# midi_block_R2_1.net
KiCad netlist of a schematic drawn in EAGLE
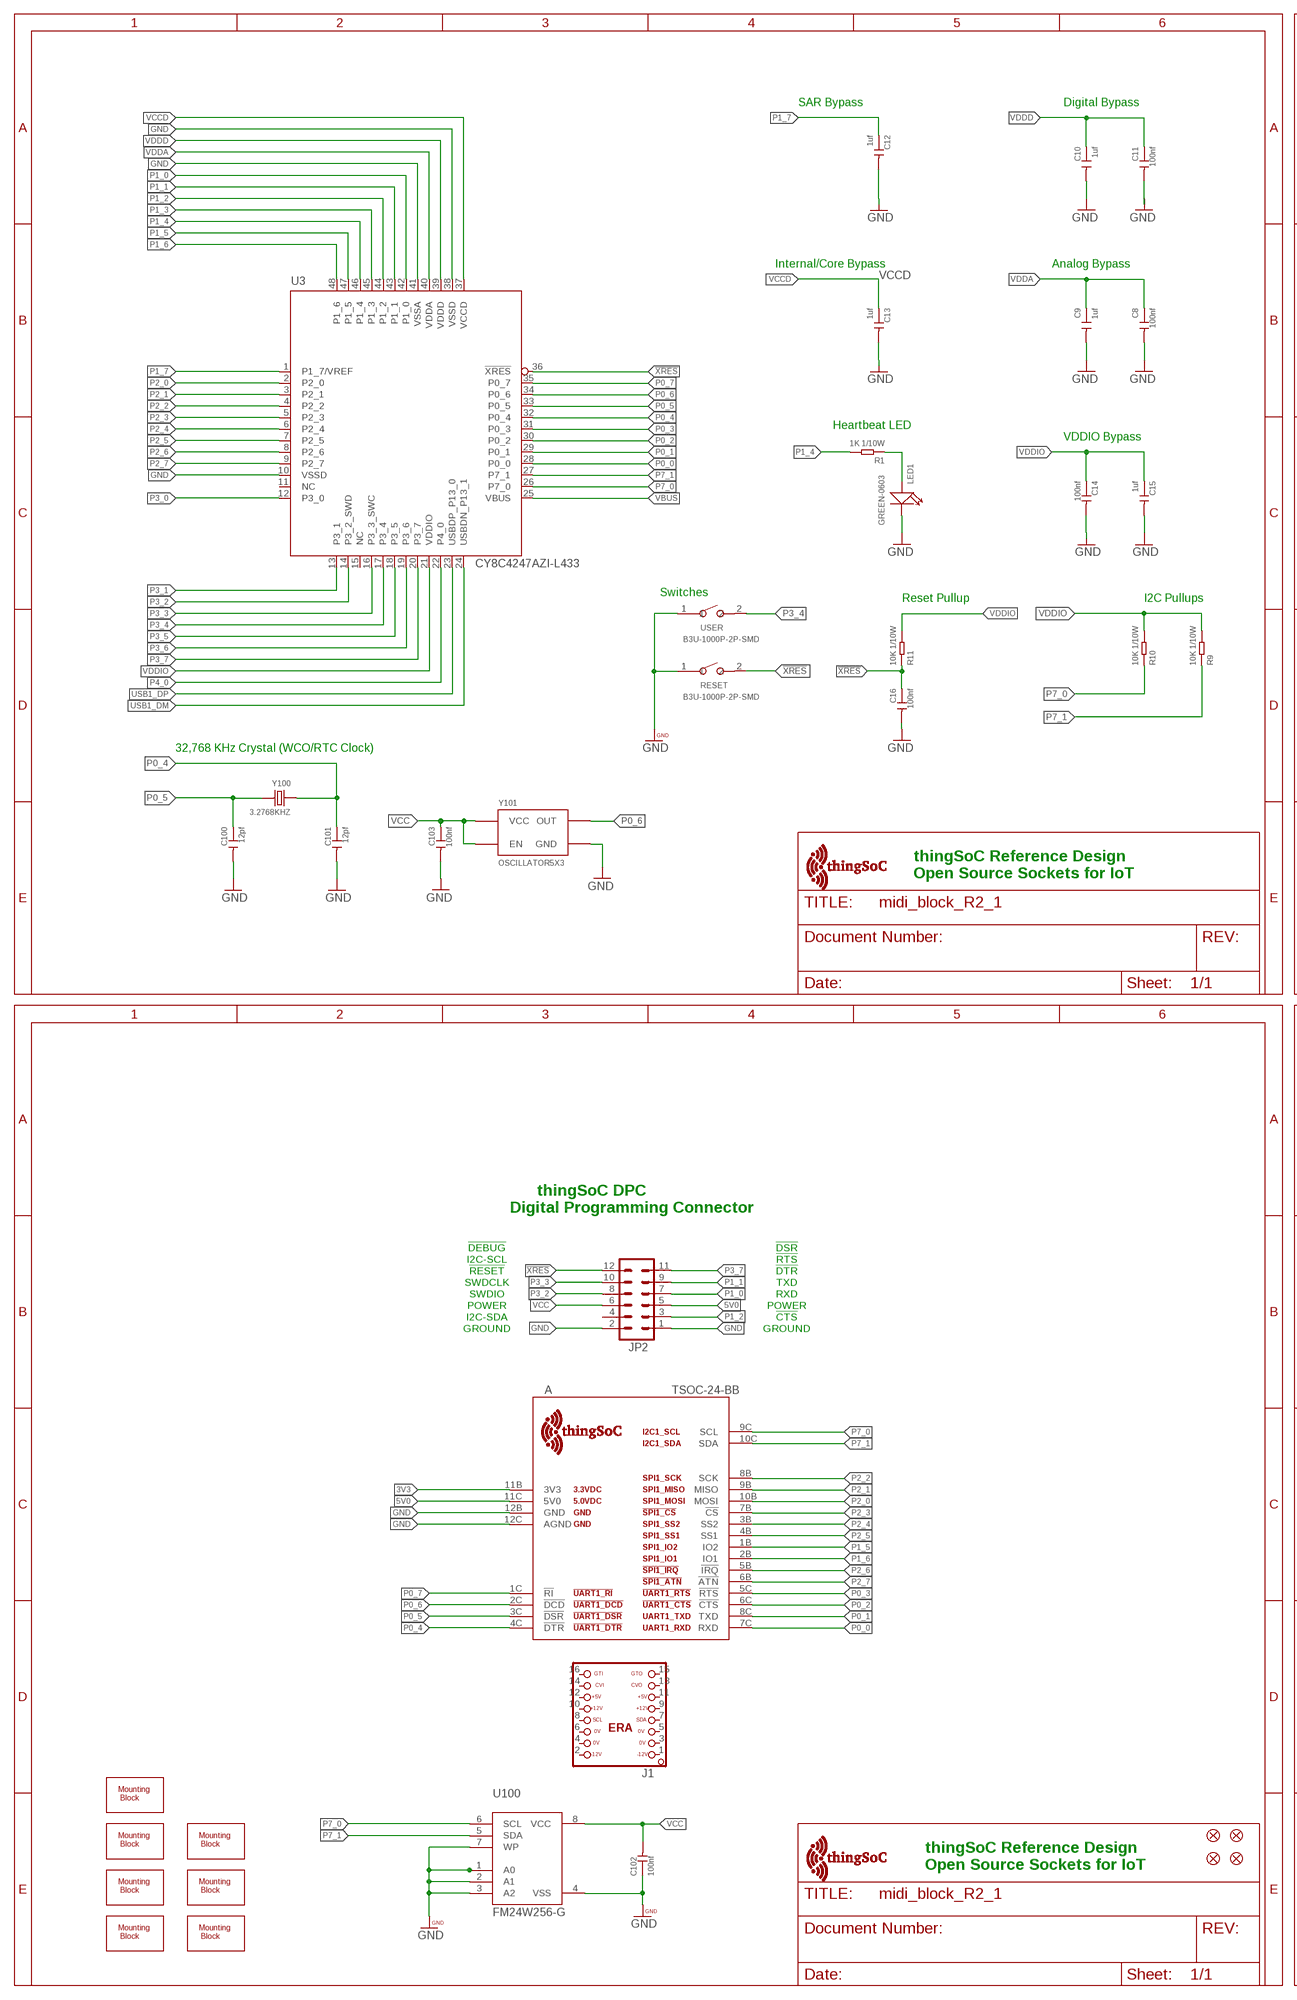
[diagram p0: schematic, sheet 1, part 1 of 2]
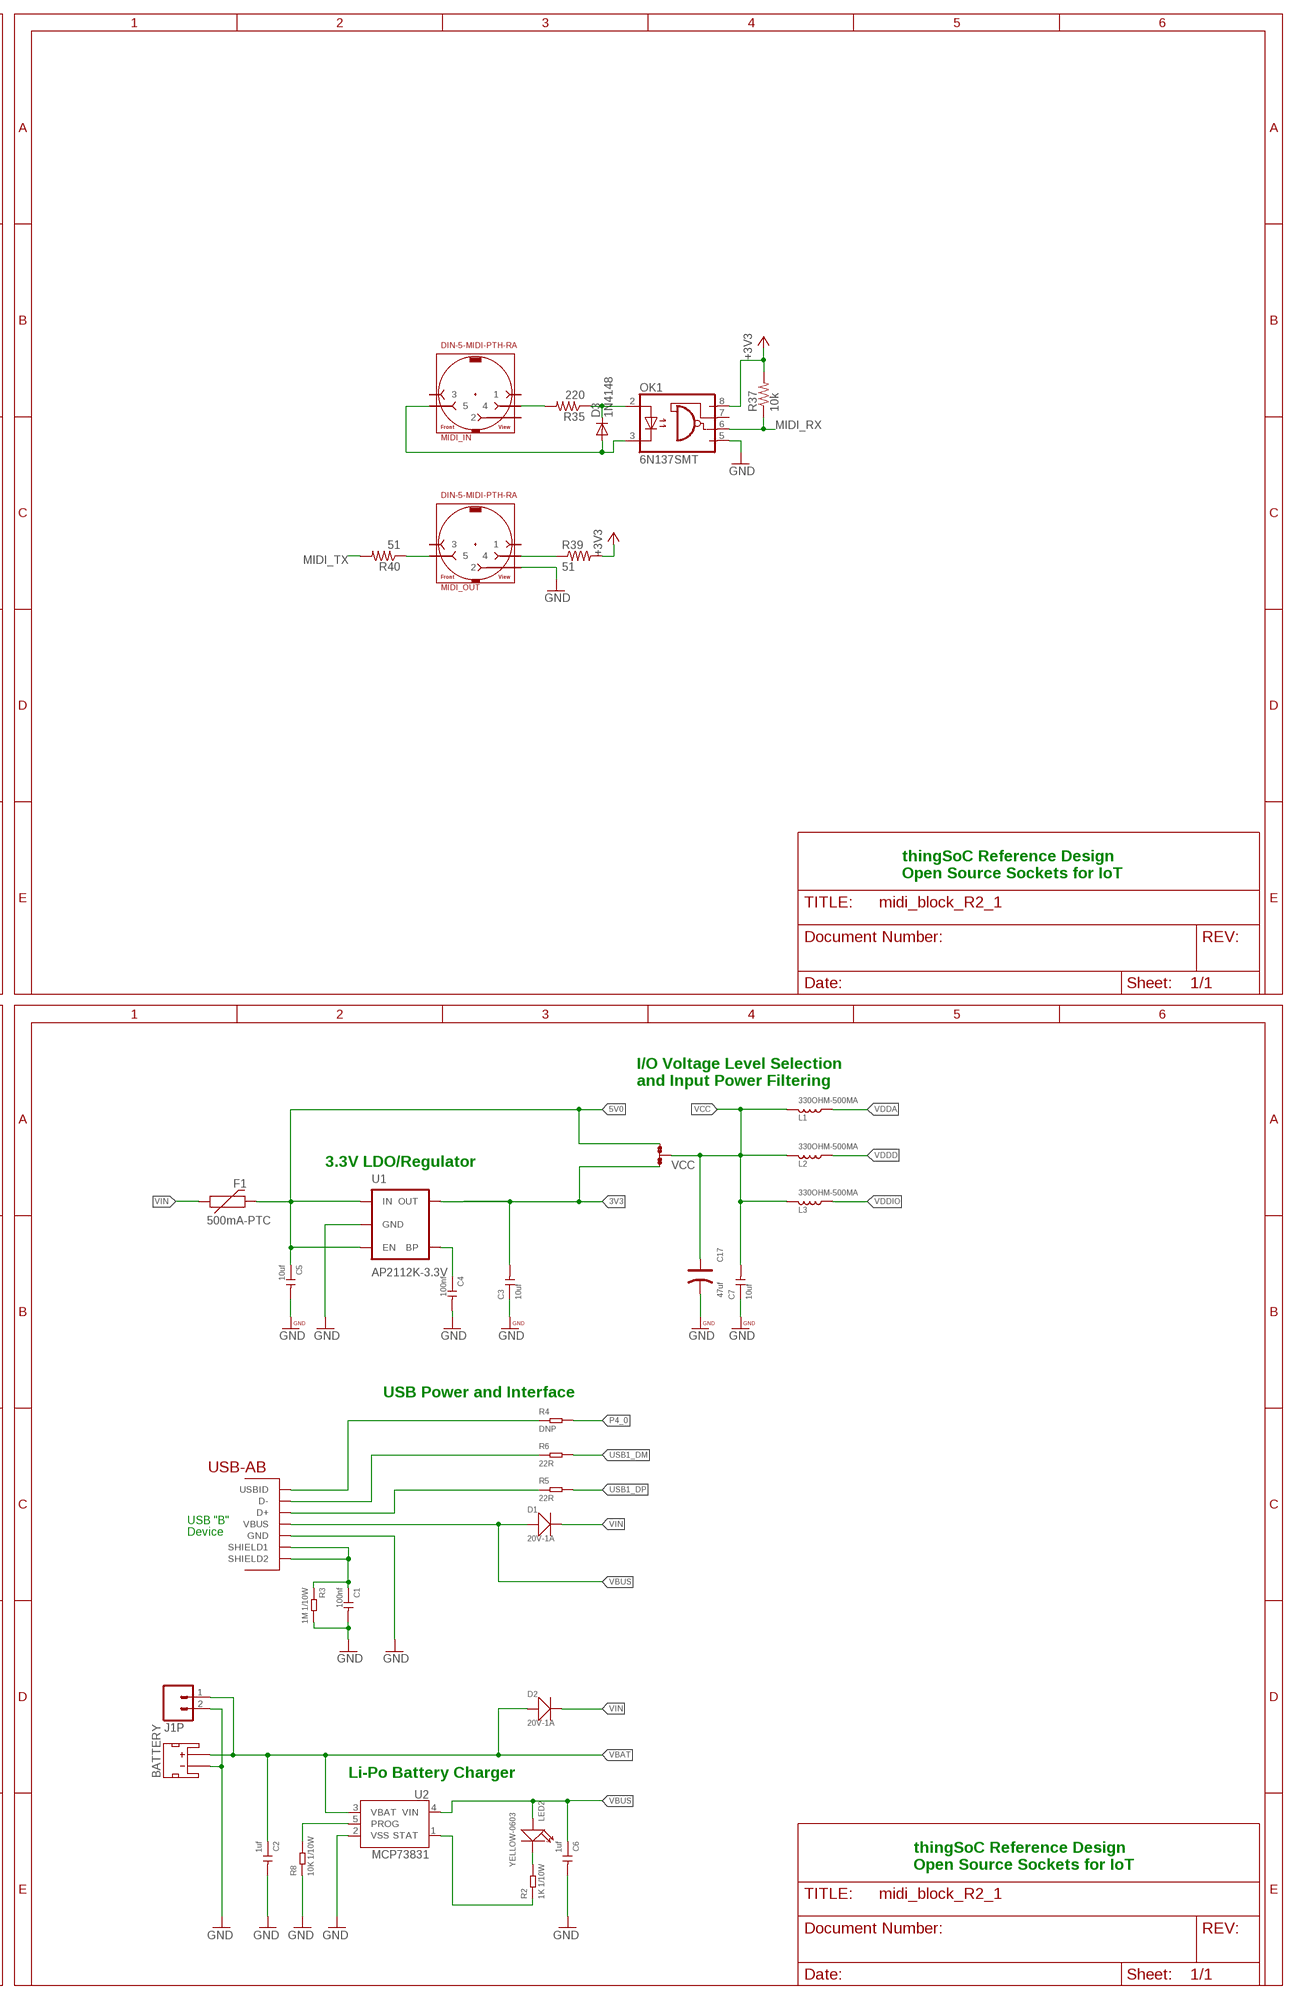
[diagram p1: schematic, sheet 1, part 2 of 2]

(export (version "E")
  (design (tool "Eeschema 10.0.6"))
  (components
    (comp (ref "A")
      (value "TSOC-24-BB")
      (footprint "eagle-import:TSOC-BB-S24")
      (libsource (lib "eagle-import") (part "TSOC-24-BB"))
    )
    (comp (ref "BATTERY")
      (value "JST_2MM_MALE")
      (footprint "eagle-import:JST-2-SMD")
      (libsource (lib "eagle-import") (part "JST_2MM_MALE"))
    )
    (comp (ref "C1")
      (value "100nf")
      (footprint "eagle-import:C0603")
      (fields (field (name "MPN") "CC0603KRX7R9BB104"))
      (libsource (lib "eagle-import") (part "CERAMIC-100NF-50V-10%-X7R(0603)"))
    )
    (comp (ref "C2")
      (value "1uf")
      (footprint "eagle-import:C0603")
      (fields (field (name "MPN") "CC0603KRX7R8BB105"))
      (libsource (lib "eagle-import") (part "CERAMIC-1UF-25V-10%-X7R(0603)"))
    )
    (comp (ref "C3")
      (value "10uf")
      (footprint "eagle-import:C0603")
      (fields (field (name "MPN") "CC0603KRX5R6BB106"))
      (libsource (lib "eagle-import") (part "CERAMIC-10UF-10V-10%-X5R(0603)"))
    )
    (comp (ref "C4")
      (value "100nf")
      (footprint "eagle-import:C0603")
      (fields (field (name "MPN") "CC0603KRX7R9BB104"))
      (libsource (lib "eagle-import") (part "CERAMIC-100NF-50V-10%-X7R(0603)"))
    )
    (comp (ref "C5")
      (value "10uf")
      (footprint "eagle-import:C0603")
      (fields (field (name "MPN") "CC0603KRX5R6BB106"))
      (libsource (lib "eagle-import") (part "CERAMIC-10UF-10V-10%-X5R(0603)"))
    )
    (comp (ref "C6")
      (value "1uf")
      (footprint "eagle-import:C0603")
      (fields (field (name "MPN") "CC0603KRX7R8BB105"))
      (libsource (lib "eagle-import") (part "CERAMIC-1UF-25V-10%-X7R(0603)"))
    )
    (comp (ref "C7")
      (value "10uf")
      (footprint "eagle-import:C0603")
      (fields (field (name "MPN") "CC0603KRX5R6BB106"))
      (libsource (lib "eagle-import") (part "CERAMIC-10UF-10V-10%-X5R(0603)"))
    )
    (comp (ref "C8")
      (value "100nf")
      (footprint "eagle-import:C0603")
      (fields (field (name "MPN") "CC0603KRX7R9BB104"))
      (libsource (lib "eagle-import") (part "CERAMIC-100NF-50V-10%-X7R(0603)"))
    )
    (comp (ref "C9")
      (value "1uf")
      (footprint "eagle-import:C0603")
      (fields (field (name "MPN") "CC0603KRX7R8BB105"))
      (libsource (lib "eagle-import") (part "CERAMIC-1UF-25V-10%-X7R(0603)"))
    )
    (comp (ref "C10")
      (value "1uf")
      (footprint "eagle-import:C0603")
      (fields (field (name "MPN") "CC0603KRX7R8BB105"))
      (libsource (lib "eagle-import") (part "CERAMIC-1UF-25V-10%-X7R(0603)"))
    )
    (comp (ref "C11")
      (value "100nf")
      (footprint "eagle-import:C0603")
      (fields (field (name "MPN") "CC0603KRX7R9BB104"))
      (libsource (lib "eagle-import") (part "CERAMIC-100NF-50V-10%-X7R(0603)"))
    )
    (comp (ref "C12")
      (value "1uf")
      (footprint "eagle-import:C0603")
      (fields (field (name "MPN") "CC0603KRX7R8BB105"))
      (libsource (lib "eagle-import") (part "CERAMIC-1UF-25V-10%-X7R(0603)"))
    )
    (comp (ref "C13")
      (value "1uf")
      (footprint "eagle-import:C0603")
      (fields (field (name "MPN") "CC0603KRX7R8BB105"))
      (libsource (lib "eagle-import") (part "CERAMIC-1UF-25V-10%-X7R(0603)"))
    )
    (comp (ref "C14")
      (value "100nf")
      (footprint "eagle-import:C0603")
      (fields (field (name "MPN") "CC0603KRX7R9BB104"))
      (libsource (lib "eagle-import") (part "CERAMIC-100NF-50V-10%-X7R(0603)"))
    )
    (comp (ref "C15")
      (value "1uf")
      (footprint "eagle-import:C0603")
      (fields (field (name "MPN") "CC0603KRX7R8BB105"))
      (libsource (lib "eagle-import") (part "CERAMIC-1UF-25V-10%-X7R(0603)"))
    )
    (comp (ref "C16")
      (value "100nf")
      (footprint "eagle-import:C0603")
      (fields (field (name "MPN") "CC0603KRX7R9BB104"))
      (libsource (lib "eagle-import") (part "CERAMIC-100NF-50V-10%-X7R(0603)"))
    )
    (comp (ref "C17")
      (value "47uf")
      (footprint "eagle-import:AVX-A")
      (fields (field (name "MPN") "TAJA476*006#NJ"))
      (libsource (lib "eagle-import") (part "TANTALUM-SMD-47UF-6.3V(AVX-A)"))
    )
    (comp (ref "C100")
      (value "12pf")
      (footprint "eagle-import:C0603")
      (fields (field (name "MPN") "CC0603JRNPO9BN120"))
      (libsource (lib "eagle-import") (part "CERAMIC-12PF-50V-5%-NPO(0603)"))
    )
    (comp (ref "C101")
      (value "12pf")
      (footprint "eagle-import:C0603")
      (fields (field (name "MPN") "CC0603JRNPO9BN120"))
      (libsource (lib "eagle-import") (part "CERAMIC-12PF-50V-5%-NPO(0603)"))
    )
    (comp (ref "C102")
      (value "100nf")
      (footprint "eagle-import:C0603")
      (fields (field (name "MPN") "CC0603KRX7R9BB104"))
      (libsource (lib "eagle-import") (part "CERAMIC-100NF-50V-10%-X7R(0603)"))
    )
    (comp (ref "C103")
      (value "100nf")
      (footprint "eagle-import:C0603")
      (fields (field (name "MPN") "CC0603KRX7R9BB104"))
      (libsource (lib "eagle-import") (part "CERAMIC-100NF-50V-10%-X7R(0603)"))
    )
    (comp (ref "D1")
      (value "20V-1A")
      (footprint "eagle-import:SOD-123")
      (fields (field (name "MPN") "B5819W"))
      (libsource (lib "eagle-import") (part "SMD-DIODE-SCHOTTKY-20V-1A(SOD-123)"))
    )
    (comp (ref "D2")
      (value "20V-1A")
      (footprint "eagle-import:SOD-123")
      (fields (field (name "MPN") "B5819W"))
      (libsource (lib "eagle-import") (part "SMD-DIODE-SCHOTTKY-20V-1A(SOD-123)"))
    )
    (comp (ref "D3")
      (value "1N4148")
      (footprint "eagle-import:SOD323-W")
      (libsource (lib "eagle-import") (part "DIODE-SOD323-W"))
    )
    (comp (ref "F1")
      (value "500mA-PTC")
      (footprint "eagle-import:PTC-1206")
      (libsource (lib "eagle-import") (part "PTCSMD"))
    )
    (comp (ref "FID1")
      (value "FIDUCIALUFIDUCIAL")
      (footprint "eagle-import:MICRO-FIDUCIAL")
      (libsource (lib "eagle-import") (part "FIDUCIALUFIDUCIAL"))
    )
    (comp (ref "FID2")
      (value "FIDUCIALUFIDUCIAL")
      (footprint "eagle-import:MICRO-FIDUCIAL")
      (libsource (lib "eagle-import") (part "FIDUCIALUFIDUCIAL"))
    )
    (comp (ref "FID3")
      (value "FIDUCIALUFIDUCIAL")
      (footprint "eagle-import:MICRO-FIDUCIAL")
      (libsource (lib "eagle-import") (part "FIDUCIALUFIDUCIAL"))
    )
    (comp (ref "FID4")
      (value "FIDUCIALUFIDUCIAL")
      (footprint "eagle-import:MICRO-FIDUCIAL")
      (libsource (lib "eagle-import") (part "FIDUCIALUFIDUCIAL"))
    )
    (comp (ref "J1")
      (value "ERA-SMD")
      (footprint "eagle-import:ERA-SMD")
      (libsource (lib "eagle-import") (part "ERA-SMD"))
    )
    (comp (ref "J1P")
      (value "M02-JST-2-PTH-NO_SILK")
      (footprint "eagle-import:JST-2-PTH-NS")
      (libsource (lib "eagle-import") (part "M02-JST-2-PTH-NO_SILK"))
    )
    (comp (ref "JP2")
      (value "M06X2FEMALE-SMT")
      (footprint "eagle-import:2X6_SMD")
      (libsource (lib "eagle-import") (part "M06X2FEMALE-SMT"))
    )
    (comp (ref "L1")
      (value "330OHM-500MA")
      (footprint "eagle-import:L0603")
      (fields (field (name "MPN") "BLM18AG121SN1D"))
      (libsource (lib "eagle-import") (part "SMD-FERRITE-CHIP-120-OHM-500MA(0603)"))
    )
    (comp (ref "L2")
      (value "330OHM-500MA")
      (footprint "eagle-import:L0603")
      (fields (field (name "MPN") "BLM18AG121SN1D"))
      (libsource (lib "eagle-import") (part "SMD-FERRITE-CHIP-120-OHM-500MA(0603)"))
    )
    (comp (ref "L3")
      (value "330OHM-500MA")
      (footprint "eagle-import:L0603")
      (fields (field (name "MPN") "BLM18AG121SN1D"))
      (libsource (lib "eagle-import") (part "SMD-FERRITE-CHIP-120-OHM-500MA(0603)"))
    )
    (comp (ref "LED1")
      (value "GREEN-0603")
      (footprint "eagle-import:LED-0603")
      (fields (field (name "MPN") "19-217-G7C-AN1P2-3T"))
      (libsource (lib "eagle-import") (part "SMD-LED-CLEAR-GREEN(0603)"))
    )
    (comp (ref "LED2")
      (value "YELLOW-0603")
      (footprint "eagle-import:LED-0603")
      (fields (field (name "MPN") "19-217-Y5C-AM1N1VY-3T"))
      (libsource (lib "eagle-import") (part "SMD-LED-CLEAR-YELLOW(0603)"))
    )
    (comp (ref "MIDI_IN")
      (value "DIN-5-MIDI-PTH-RA")
      (footprint "eagle-import:DIN-5-PTH-RA-SUPPORT")
      (libsource (lib "eagle-import") (part "DIN-5-MIDI-PTH-RA"))
    )
    (comp (ref "MIDI_OUT")
      (value "DIN-5-MIDI-PTH-RA")
      (footprint "eagle-import:DIN-5-PTH-RA-SUPPORT")
      (libsource (lib "eagle-import") (part "DIN-5-MIDI-PTH-RA"))
    )
    (comp (ref "OK1")
      (value "6N137SMT")
      (footprint "eagle-import:DIL8-SMD")
      (libsource (lib "eagle-import") (part "6N137SMT"))
    )
    (comp (ref "R1")
      (value "1K 1/10W")
      (footprint "eagle-import:R0603")
      (fields (field (name "MPN") "RC0603JR-071KL"))
      (libsource (lib "eagle-import") (part "SMD-RES-1K-5%-1/10W(0603)"))
    )
    (comp (ref "R2")
      (value "1K 1/10W")
      (footprint "eagle-import:R0603")
      (fields (field (name "MPN") "RC0603JR-071KL"))
      (libsource (lib "eagle-import") (part "SMD-RES-1K-5%-1/10W(0603)"))
    )
    (comp (ref "R3")
      (value "1M 1/10W")
      (footprint "eagle-import:R0603")
      (fields (field (name "MPN") "RC0603JR-071ML"))
      (libsource (lib "eagle-import") (part "SMD-RES-1M-5%-1/10W(0603)"))
    )
    (comp (ref "R4")
      (value "DNP")
      (footprint "eagle-import:R0603")
      (fields (field (name "MPN") "RC0603JR-0722RL"))
      (libsource (lib "eagle-import") (part "SMD-RES-22R-5%-1/10W(0603)"))
    )
    (comp (ref "R5")
      (value "22R")
      (footprint "eagle-import:R0603")
      (fields (field (name "MPN") "RC0603JR-0722RL"))
      (libsource (lib "eagle-import") (part "SMD-RES-22R-5%-1/10W(0603)"))
    )
    (comp (ref "R6")
      (value "22R")
      (footprint "eagle-import:R0603")
      (fields (field (name "MPN") "RC0603JR-0722RL"))
      (libsource (lib "eagle-import") (part "SMD-RES-22R-5%-1/10W(0603)"))
    )
    (comp (ref "R8")
      (value "10K 1/10W")
      (footprint "eagle-import:R0603")
      (fields (field (name "MPN") "RC0603JR-0710KL"))
      (libsource (lib "eagle-import") (part "SMD-RES-10K-5%-1/10W(0603)"))
    )
    (comp (ref "R9")
      (value "10K 1/10W")
      (footprint "eagle-import:R0603")
      (fields (field (name "MPN") "RC0603JR-0710KL"))
      (libsource (lib "eagle-import") (part "SMD-RES-10K-5%-1/10W(0603)"))
    )
    (comp (ref "R10")
      (value "10K 1/10W")
      (footprint "eagle-import:R0603")
      (fields (field (name "MPN") "RC0603JR-0710KL"))
      (libsource (lib "eagle-import") (part "SMD-RES-10K-5%-1/10W(0603)"))
    )
    (comp (ref "R11")
      (value "10K 1/10W")
      (footprint "eagle-import:R0603")
      (fields (field (name "MPN") "RC0603JR-0710KL"))
      (libsource (lib "eagle-import") (part "SMD-RES-10K-5%-1/10W(0603)"))
    )
    (comp (ref "R35")
      (value "220")
      (footprint "eagle-import:R0603")
      (libsource (lib "eagle-import") (part "R-US_R0603"))
    )
    (comp (ref "R37")
      (value "10k")
      (footprint "eagle-import:R0603")
      (libsource (lib "eagle-import") (part "R-US_R0603"))
    )
    (comp (ref "R39")
      (value "51")
      (footprint "eagle-import:R0603")
      (libsource (lib "eagle-import") (part "R-US_R0603"))
    )
    (comp (ref "R40")
      (value "51")
      (footprint "eagle-import:R0603")
      (libsource (lib "eagle-import") (part "R-US_R0603"))
    )
    (comp (ref "RESET")
      (value "B3U-1000P-2P-SMD")
      (footprint "eagle-import:SW2-2.6-3.0X2.5X1.2+0.4MM")
      (libsource (lib "eagle-import") (part "SMD-BUTTON(2P-3.0X2.5X1.2+0.4MM)-B3U-1000P-2P-SMD"))
    )
    (comp (ref "U$1")
      (value "PCB-MB-SIDE")
      (footprint "eagle-import:PCB-MB-01-SIDE")
      (libsource (lib "eagle-import") (part "PCB-MB-SIDE"))
    )
    (comp (ref "U$7")
      (value "PCB-MB-SIDE")
      (footprint "eagle-import:PCB-MB-01-SIDE")
      (libsource (lib "eagle-import") (part "PCB-MB-SIDE"))
    )
    (comp (ref "U$8")
      (value "PCB-MB-SIDE")
      (footprint "eagle-import:PCB-MB-01-SIDE")
      (libsource (lib "eagle-import") (part "PCB-MB-SIDE"))
    )
    (comp (ref "U$9")
      (value "PCB-MB-SIDE")
      (footprint "eagle-import:PCB-MB-01-SIDE")
      (libsource (lib "eagle-import") (part "PCB-MB-SIDE"))
    )
    (comp (ref "U$10")
      (value "PCB-MB-SIDE")
      (footprint "eagle-import:PCB-MB-01-SIDE")
      (libsource (lib "eagle-import") (part "PCB-MB-SIDE"))
    )
    (comp (ref "U$11")
      (value "PCB-MB-SIDE")
      (footprint "eagle-import:PCB-MB-01-SIDE")
      (libsource (lib "eagle-import") (part "PCB-MB-SIDE"))
    )
    (comp (ref "U$12")
      (value "PCB-MB-SIDE")
      (footprint "eagle-import:PCB-MB-01-SIDE")
      (libsource (lib "eagle-import") (part "PCB-MB-SIDE"))
    )
    (comp (ref "U$100")
      (value "TSOC-LOGO-LRG")
      (footprint "eagle-import:TSOC-LOGO-LRG")
      (libsource (lib "eagle-import") (part "TSOC-LOGO-LRG"))
    )
    (comp (ref "U$101")
      (value "TSOC-LOGO-SMALL")
      (footprint "eagle-import:TSOC-LOGO-SML")
      (libsource (lib "eagle-import") (part "TSOC-LOGO-SMALL"))
    )
    (comp (ref "U1")
      (value "AP2112K-3.3V")
      (footprint "eagle-import:SOT23-5")
      (libsource (lib "eagle-import") (part "V_REG_LDOSMD"))
    )
    (comp (ref "U2")
      (value "MCP73831")
      (footprint "eagle-import:SOT23-5")
      (libsource (lib "eagle-import") (part "MCP73831"))
    )
    (comp (ref "U3")
      (value "CY8C4247AZI-L433")
      (footprint "eagle-import:TQFP-7X7-48")
      (libsource (lib "eagle-import") (part "CY8C4247AZI-L433"))
    )
    (comp (ref "U100")
      (value "FM24W256-G")
      (footprint "eagle-import:SO08")
      (libsource (lib "eagle-import") (part "FM24W256-G"))
    )
    (comp (ref "USB")
      (value "USB_AB")
      (footprint "eagle-import:USB-AB-MICRO-SMD")
      (libsource (lib "eagle-import") (part "USB_AB"))
    )
    (comp (ref "USER")
      (value "B3U-1000P-2P-SMD")
      (footprint "eagle-import:SW2-2.6-3.0X2.5X1.2+0.4MM")
      (libsource (lib "eagle-import") (part "SMD-BUTTON(2P-3.0X2.5X1.2+0.4MM)-B3U-1000P-2P-SMD"))
    )
    (comp (ref "VCC")
      (value "JMP-3-1_2")
      (footprint "eagle-import:JMP-3-1_2")
      (libsource (lib "eagle-import") (part "JMP-3-1_2"))
    )
    (comp (ref "Y100")
      (value "3.2768KHZ")
      (footprint "eagle-import:X2-SMD-L2.0X1.2X0.55MM")
      (fields (field (name "MPN") "FC-12M"))
      (libsource (lib "eagle-import") (part "SMD-CRYSTAL-32.768KHZ-12.5PF-20PPM-90K(2P-L2.0X1.2MM)"))
    )
    (comp (ref "Y101")
      (value "OSCILLATOR5X3")
      (footprint "eagle-import:CRYSTAL-SMD-5X3")
      (libsource (lib "eagle-import") (part "OSCILLATOR5X3"))
    )
  )
  (nets
    (net (code "1") (name "+3V3") (class "Default")
      (node (ref "OK1") (pin "8") (pinfunction "VCC_8") (pintype "passive"))
      (node (ref "R37") (pin "2") (pinfunction "2_2") (pintype "passive"))
      (node (ref "R39") (pin "2") (pinfunction "2_2") (pintype "passive"))
    )
    (net (code "2") (name "/MIDI_RX") (class "Default")
      (node (ref "OK1") (pin "6") (pinfunction "VO_6") (pintype "passive"))
      (node (ref "R37") (pin "1") (pinfunction "1_1") (pintype "passive"))
    )
    (net (code "3") (name "/MIDI_TX") (class "Default")
      (node (ref "R40") (pin "2") (pinfunction "2_2") (pintype "passive"))
    )
    (net (code "4") (name "/~{XRES}") (class "Default")
      (node (ref "C16") (pin "1") (pinfunction "1_1") (pintype "passive"))
      (node (ref "JP2") (pin "12") (pinfunction "12_12") (pintype "passive"))
      (node (ref "R11") (pin "1") (pinfunction "1_1") (pintype "passive"))
      (node (ref "RESET") (pin "2") (pinfunction "2_2") (pintype "bidirectional"))
      (node (ref "U3") (pin "36") (pinfunction "~{XRES}_36") (pintype "bidirectional"))
    )
    (net (code "5") (name "3V3") (class "Default")
      (node (ref "A") (pin "11B") (pinfunction "3V3_11B") (pintype "bidirectional"))
      (node (ref "C3") (pin "2") (pinfunction "2_2") (pintype "passive"))
      (node (ref "U1") (pin "5") (pinfunction "OUT_5") (pintype "passive"))
      (node (ref "VCC") (pin "1") (pinfunction "1_1") (pintype "passive"))
    )
    (net (code "6") (name "5V0") (class "Default")
      (node (ref "A") (pin "11C") (pinfunction "5V0_11C") (pintype "bidirectional"))
      (node (ref "C5") (pin "1") (pinfunction "1_1") (pintype "passive"))
      (node (ref "F1") (pin "2") (pinfunction "2_2") (pintype "bidirectional"))
      (node (ref "JP2") (pin "5") (pinfunction "5_5") (pintype "passive"))
      (node (ref "U1") (pin "1") (pinfunction "IN_1") (pintype "input"))
      (node (ref "U1") (pin "3") (pinfunction "EN_3") (pintype "input"))
      (node (ref "VCC") (pin "3") (pinfunction "3_3") (pintype "passive"))
    )
    (net (code "7") (name "GND") (class "Default")
      (node (ref "A") (pin "12B") (pinfunction "GND_12B") (pintype "bidirectional"))
      (node (ref "A") (pin "12C") (pinfunction "AGND_12C") (pintype "bidirectional"))
      (node (ref "BATTERY") (pin "1") (pinfunction "-_1") (pintype "bidirectional"))
      (node (ref "C1") (pin "2") (pinfunction "2_2") (pintype "passive"))
      (node (ref "C10") (pin "2") (pinfunction "2_2") (pintype "passive"))
      (node (ref "C100") (pin "2") (pinfunction "2_2") (pintype "passive"))
      (node (ref "C101") (pin "2") (pinfunction "2_2") (pintype "passive"))
      (node (ref "C102") (pin "1") (pinfunction "1_1") (pintype "passive"))
      (node (ref "C103") (pin "2") (pinfunction "2_2") (pintype "passive"))
      (node (ref "C11") (pin "2") (pinfunction "2_2") (pintype "passive"))
      (node (ref "C12") (pin "2") (pinfunction "2_2") (pintype "passive"))
      (node (ref "C13") (pin "2") (pinfunction "2_2") (pintype "passive"))
      (node (ref "C14") (pin "2") (pinfunction "2_2") (pintype "passive"))
      (node (ref "C15") (pin "2") (pinfunction "2_2") (pintype "passive"))
      (node (ref "C16") (pin "2") (pinfunction "2_2") (pintype "passive"))
      (node (ref "C17") (pin "-") (pinfunction "-_-") (pintype "passive"))
      (node (ref "C2") (pin "2") (pinfunction "2_2") (pintype "passive"))
      (node (ref "C3") (pin "1") (pinfunction "1_1") (pintype "passive"))
      (node (ref "C4") (pin "2") (pinfunction "2_2") (pintype "passive"))
      (node (ref "C5") (pin "2") (pinfunction "2_2") (pintype "passive"))
      (node (ref "C6") (pin "2") (pinfunction "2_2") (pintype "passive"))
      (node (ref "C7") (pin "1") (pinfunction "1_1") (pintype "passive"))
      (node (ref "C8") (pin "2") (pinfunction "2_2") (pintype "passive"))
      (node (ref "C9") (pin "2") (pinfunction "2_2") (pintype "passive"))
      (node (ref "J1P") (pin "2") (pinfunction "2_2") (pintype "passive"))
      (node (ref "JP2") (pin "1") (pinfunction "1_1") (pintype "passive"))
      (node (ref "JP2") (pin "2") (pinfunction "2_2") (pintype "passive"))
      (node (ref "LED1") (pin "-") (pinfunction "-_-") (pintype "passive"))
      (node (ref "MIDI_OUT") (pin "2") (pinfunction "2_2") (pintype "bidirectional"))
      (node (ref "OK1") (pin "5") (pinfunction "GND_5") (pintype "passive"))
      (node (ref "R3") (pin "2") (pinfunction "2_2") (pintype "passive"))
      (node (ref "R8") (pin "1") (pinfunction "1_1") (pintype "passive"))
      (node (ref "RESET") (pin "1") (pinfunction "1_1") (pintype "bidirectional"))
      (node (ref "U1") (pin "2") (pinfunction "GND_2") (pintype "input"))
      (node (ref "U100") (pin "1") (pinfunction "A0_1") (pintype "bidirectional"))
      (node (ref "U100") (pin "2") (pinfunction "A1_2") (pintype "bidirectional"))
      (node (ref "U100") (pin "3") (pinfunction "A2_3") (pintype "bidirectional"))
      (node (ref "U100") (pin "4") (pinfunction "VSS_4") (pintype "power_in"))
      (node (ref "U100") (pin "7") (pinfunction "WP_7") (pintype "bidirectional"))
      (node (ref "U2") (pin "2") (pinfunction "VSS_2") (pintype "power_in"))
      (node (ref "U3") (pin "10") (pinfunction "VSSD_10") (pintype "bidirectional"))
      (node (ref "U3") (pin "38") (pinfunction "VSSD_38") (pintype "bidirectional"))
      (node (ref "U3") (pin "41") (pinfunction "VSSA_41") (pintype "bidirectional"))
      (node (ref "USB") (pin "GND") (pinfunction "GND_GND") (pintype "bidirectional"))
      (node (ref "USER") (pin "1") (pinfunction "1_1") (pintype "bidirectional"))
      (node (ref "Y101") (pin "2") (pinfunction "GND_2") (pintype "bidirectional"))
    )
    (net (code "8") (name "Net-(C1-Pad1)") (class "Default")
      (node (ref "C1") (pin "1") (pinfunction "1_1") (pintype "passive"))
      (node (ref "R3") (pin "1") (pinfunction "1_1") (pintype "passive"))
      (node (ref "USB") (pin "SHIELD1") (pinfunction "SHIELD1_SHIELD1") (pintype "bidirectional"))
      (node (ref "USB") (pin "SHIELD2") (pinfunction "SHIELD2_SHIELD2") (pintype "bidirectional"))
    )
    (net (code "9") (name "Net-(LED1-Pad+)") (class "Default")
      (node (ref "LED1") (pin "+") (pinfunction "+_+") (pintype "passive"))
      (node (ref "R1") (pin "1") (pinfunction "1_1") (pintype "passive"))
    )
    (net (code "10") (name "Net-(LED2-Pad-)") (class "Default")
      (node (ref "LED2") (pin "-") (pinfunction "-_-") (pintype "passive"))
      (node (ref "R2") (pin "2") (pinfunction "2_2") (pintype "passive"))
    )
    (net (code "11") (name "Net-(MIDI_IN-Pad4)") (class "Default")
      (node (ref "MIDI_IN") (pin "4") (pinfunction "4_4") (pintype "bidirectional"))
      (node (ref "R35") (pin "2") (pinfunction "2_2") (pintype "passive"))
    )
    (net (code "12") (name "Net-(MIDI_OUT-Pad4)") (class "Default")
      (node (ref "MIDI_OUT") (pin "4") (pinfunction "4_4") (pintype "bidirectional"))
      (node (ref "R39") (pin "1") (pinfunction "1_1") (pintype "passive"))
    )
    (net (code "13") (name "Net-(MIDI_OUT-Pad5)") (class "Default")
      (node (ref "MIDI_OUT") (pin "5") (pinfunction "5_5") (pintype "bidirectional"))
      (node (ref "R40") (pin "1") (pinfunction "1_1") (pintype "passive"))
    )
    (net (code "14") (name "Net-(OK1-A)") (class "Default")
      (node (ref "D3") (pin "C") (pinfunction "C_C") (pintype "passive"))
      (node (ref "OK1") (pin "2") (pinfunction "A_2") (pintype "passive"))
      (node (ref "R35") (pin "1") (pinfunction "1_1") (pintype "passive"))
    )
    (net (code "15") (name "Net-(OK1-C)") (class "Default")
      (node (ref "D3") (pin "A") (pinfunction "A_A") (pintype "passive"))
      (node (ref "MIDI_IN") (pin "5") (pinfunction "5_5") (pintype "bidirectional"))
      (node (ref "OK1") (pin "3") (pinfunction "C_3") (pintype "passive"))
    )
    (net (code "16") (name "Net-(R5-Pad1)") (class "Default")
      (node (ref "R5") (pin "1") (pinfunction "1_1") (pintype "passive"))
      (node (ref "USB") (pin "D+") (pinfunction "D+_D+") (pintype "bidirectional"))
    )
    (net (code "17") (name "Net-(R6-Pad1)") (class "Default")
      (node (ref "R6") (pin "1") (pinfunction "1_1") (pintype "passive"))
      (node (ref "USB") (pin "D-") (pinfunction "D-_D-") (pintype "bidirectional"))
    )
    (net (code "18") (name "Net-(U1-BP)") (class "Default")
      (node (ref "C4") (pin "1") (pinfunction "1_1") (pintype "passive"))
      (node (ref "U1") (pin "4") (pinfunction "BP_4") (pintype "input"))
    )
    (net (code "19") (name "Net-(U2-PROG)") (class "Default")
      (node (ref "R8") (pin "2") (pinfunction "2_2") (pintype "passive"))
      (node (ref "U2") (pin "5") (pinfunction "PROG_5") (pintype "input"))
    )
    (net (code "20") (name "Net-(U2-STAT)") (class "Default")
      (node (ref "R2") (pin "1") (pinfunction "1_1") (pintype "passive"))
      (node (ref "U2") (pin "1") (pinfunction "STAT_1") (pintype "output"))
    )
    (net (code "21") (name "Net-(USB-USBID)") (class "Default")
      (node (ref "R4") (pin "1") (pinfunction "1_1") (pintype "passive"))
      (node (ref "USB") (pin "ID") (pinfunction "USBID_ID") (pintype "bidirectional"))
    )
    (net (code "22") (name "P0_0") (class "Default")
      (node (ref "A") (pin "7C") (pinfunction "RXD_7C") (pintype "bidirectional"))
      (node (ref "U3") (pin "28") (pinfunction "P0_0_28") (pintype "bidirectional"))
    )
    (net (code "23") (name "P0_1") (class "Default")
      (node (ref "A") (pin "8C") (pinfunction "TXD_8C") (pintype "bidirectional"))
      (node (ref "U3") (pin "29") (pinfunction "P0_1_29") (pintype "bidirectional"))
    )
    (net (code "24") (name "P0_2") (class "Default")
      (node (ref "A") (pin "6C") (pinfunction "~{CTS}_6C") (pintype "bidirectional"))
      (node (ref "U3") (pin "30") (pinfunction "P0_2_30") (pintype "input"))
    )
    (net (code "25") (name "P0_3") (class "Default")
      (node (ref "A") (pin "5C") (pinfunction "~{RTS}_5C") (pintype "bidirectional"))
      (node (ref "U3") (pin "31") (pinfunction "P0_3_31") (pintype "bidirectional"))
    )
    (net (code "26") (name "P0_4") (class "Default")
      (node (ref "A") (pin "4C") (pinfunction "~{DTR}_4C") (pintype "bidirectional"))
      (node (ref "C101") (pin "1") (pinfunction "1_1") (pintype "passive"))
      (node (ref "U3") (pin "32") (pinfunction "P0_4_32") (pintype "bidirectional"))
      (node (ref "Y100") (pin "1") (pinfunction "1_1") (pintype "passive"))
    )
    (net (code "27") (name "P0_5") (class "Default")
      (node (ref "A") (pin "3C") (pinfunction "~{DSR}_3C") (pintype "bidirectional"))
      (node (ref "C100") (pin "1") (pinfunction "1_1") (pintype "passive"))
      (node (ref "U3") (pin "33") (pinfunction "P0_5_33") (pintype "bidirectional"))
      (node (ref "Y100") (pin "2") (pinfunction "2_2") (pintype "passive"))
    )
    (net (code "28") (name "P0_6") (class "Default")
      (node (ref "A") (pin "2C") (pinfunction "~{DCD}_2C") (pintype "bidirectional"))
      (node (ref "U3") (pin "34") (pinfunction "P0_6_34") (pintype "power_in"))
      (node (ref "Y101") (pin "3") (pinfunction "OUT_3") (pintype "bidirectional"))
    )
    (net (code "29") (name "P0_7") (class "Default")
      (node (ref "A") (pin "1C") (pinfunction "~{RI}_1C") (pintype "bidirectional"))
      (node (ref "U3") (pin "35") (pinfunction "P0_7_35") (pintype "bidirectional"))
    )
    (net (code "30") (name "P1_0") (class "Default")
      (node (ref "JP2") (pin "7") (pinfunction "7_7") (pintype "passive"))
      (node (ref "U3") (pin "42") (pinfunction "P1_0_42") (pintype "bidirectional"))
    )
    (net (code "31") (name "P1_1") (class "Default")
      (node (ref "JP2") (pin "9") (pinfunction "9_9") (pintype "passive"))
      (node (ref "U3") (pin "43") (pinfunction "P1_1_43") (pintype "bidirectional"))
    )
    (net (code "32") (name "P1_2") (class "Default")
      (node (ref "JP2") (pin "3") (pinfunction "3_3") (pintype "passive"))
      (node (ref "U3") (pin "44") (pinfunction "P1_2_44") (pintype "power_in"))
    )
    (net (code "33") (name "P1_3") (class "Default")
      (node (ref "U3") (pin "45") (pinfunction "P1_3_45") (pintype "bidirectional"))
    )
    (net (code "34") (name "P1_4") (class "Default")
      (node (ref "R1") (pin "2") (pinfunction "2_2") (pintype "passive"))
      (node (ref "U3") (pin "46") (pinfunction "P1_4_46") (pintype "bidirectional"))
    )
    (net (code "35") (name "P1_5") (class "Default")
      (node (ref "A") (pin "1B") (pinfunction "IO2_1B") (pintype "bidirectional"))
      (node (ref "U3") (pin "47") (pinfunction "P1_5_47") (pintype "bidirectional"))
    )
    (net (code "36") (name "P1_6") (class "Default")
      (node (ref "A") (pin "2B") (pinfunction "IO1_2B") (pintype "bidirectional"))
      (node (ref "U3") (pin "48") (pinfunction "P1_6_48") (pintype "bidirectional"))
    )
    (net (code "37") (name "P1_7") (class "Default")
      (node (ref "C12") (pin "1") (pinfunction "1_1") (pintype "passive"))
      (node (ref "U3") (pin "1") (pinfunction "P1_7/VREF_1") (pintype "bidirectional"))
    )
    (net (code "38") (name "P2_0") (class "Default")
      (node (ref "A") (pin "10B") (pinfunction "MOSI_10B") (pintype "bidirectional"))
      (node (ref "U3") (pin "2") (pinfunction "P2_0_2") (pintype "bidirectional"))
    )
    (net (code "39") (name "P2_1") (class "Default")
      (node (ref "A") (pin "9B") (pinfunction "MISO_9B") (pintype "bidirectional"))
      (node (ref "U3") (pin "3") (pinfunction "P2_1_3") (pintype "bidirectional"))
    )
    (net (code "40") (name "P2_2") (class "Default")
      (node (ref "A") (pin "8B") (pinfunction "SCK_8B") (pintype "bidirectional"))
      (node (ref "U3") (pin "4") (pinfunction "P2_2_4") (pintype "power_in"))
    )
    (net (code "41") (name "P2_3") (class "Default")
      (node (ref "A") (pin "7B") (pinfunction "~{CS}_7B") (pintype "bidirectional"))
      (node (ref "U3") (pin "5") (pinfunction "P2_3_5") (pintype "bidirectional"))
    )
    (net (code "42") (name "P2_4") (class "Default")
      (node (ref "A") (pin "3B") (pinfunction "SS2_3B") (pintype "bidirectional"))
      (node (ref "U3") (pin "6") (pinfunction "P2_4_6") (pintype "bidirectional"))
    )
    (net (code "43") (name "P2_5") (class "Default")
      (node (ref "A") (pin "4B") (pinfunction "SS1_4B") (pintype "bidirectional"))
      (node (ref "U3") (pin "7") (pinfunction "P2_5_7") (pintype "bidirectional"))
    )
    (net (code "44") (name "P2_6") (class "Default")
      (node (ref "A") (pin "5B") (pinfunction "~{IRQ}_5B") (pintype "bidirectional"))
      (node (ref "U3") (pin "8") (pinfunction "P2_6_8") (pintype "power_in"))
    )
    (net (code "45") (name "P2_7") (class "Default")
      (node (ref "A") (pin "6B") (pinfunction "~{ATN}_6B") (pintype "bidirectional"))
      (node (ref "U3") (pin "9") (pinfunction "P2_7_9") (pintype "bidirectional"))
    )
    (net (code "46") (name "P3_0") (class "Default")
      (node (ref "U3") (pin "12") (pinfunction "P3_0_12") (pintype "bidirectional"))
    )
    (net (code "47") (name "P3_1") (class "Default")
      (node (ref "U3") (pin "13") (pinfunction "P3_1_13") (pintype "bidirectional"))
    )
    (net (code "48") (name "P3_2") (class "Default")
      (node (ref "JP2") (pin "8") (pinfunction "8_8") (pintype "passive"))
      (node (ref "U3") (pin "14") (pinfunction "P3_2_SWD_14") (pintype "bidirectional"))
    )
    (net (code "49") (name "P3_3") (class "Default")
      (node (ref "JP2") (pin "10") (pinfunction "10_10") (pintype "passive"))
      (node (ref "U3") (pin "16") (pinfunction "P3_3_SWC_16") (pintype "bidirectional"))
    )
    (net (code "50") (name "P3_4") (class "Default")
      (node (ref "U3") (pin "17") (pinfunction "P3_4_17") (pintype "bidirectional"))
      (node (ref "USER") (pin "2") (pinfunction "2_2") (pintype "bidirectional"))
    )
    (net (code "51") (name "P3_5") (class "Default")
      (node (ref "U3") (pin "18") (pinfunction "P3_5_18") (pintype "bidirectional"))
    )
    (net (code "52") (name "P3_6") (class "Default")
      (node (ref "U3") (pin "19") (pinfunction "P3_6_19") (pintype "power_in"))
    )
    (net (code "53") (name "P3_7") (class "Default")
      (node (ref "JP2") (pin "11") (pinfunction "11_11") (pintype "passive"))
      (node (ref "U3") (pin "20") (pinfunction "P3_7_20") (pintype "bidirectional"))
    )
    (net (code "54") (name "P4_0") (class "Default")
      (node (ref "R4") (pin "2") (pinfunction "2_2") (pintype "passive"))
      (node (ref "U3") (pin "22") (pinfunction "P4_0_22") (pintype "bidirectional"))
    )
    (net (code "55") (name "P7_0") (class "Default")
      (node (ref "A") (pin "9C") (pinfunction "SCL_9C") (pintype "bidirectional"))
      (node (ref "R10") (pin "1") (pinfunction "1_1") (pintype "passive"))
      (node (ref "U100") (pin "6") (pinfunction "SCL_6") (pintype "bidirectional"))
      (node (ref "U3") (pin "26") (pinfunction "P7_0_26") (pintype "bidirectional"))
    )
    (net (code "56") (name "P7_1") (class "Default")
      (node (ref "A") (pin "10C") (pinfunction "SDA_10C") (pintype "bidirectional"))
      (node (ref "R9") (pin "1") (pinfunction "1_1") (pintype "passive"))
      (node (ref "U100") (pin "5") (pinfunction "SDA_5") (pintype "bidirectional"))
      (node (ref "U3") (pin "27") (pinfunction "P7_1_27") (pintype "bidirectional"))
    )
    (net (code "57") (name "USB1_DM") (class "Default")
      (node (ref "R6") (pin "2") (pinfunction "2_2") (pintype "passive"))
      (node (ref "U3") (pin "24") (pinfunction "USBDN_P13_1_24") (pintype "bidirectional"))
    )
    (net (code "58") (name "USB1_DP") (class "Default")
      (node (ref "R5") (pin "2") (pinfunction "2_2") (pintype "passive"))
      (node (ref "U3") (pin "23") (pinfunction "USBDP_P13_0_23") (pintype "bidirectional"))
    )
    (net (code "59") (name "VBAT") (class "Default")
      (node (ref "BATTERY") (pin "2") (pinfunction "+_2") (pintype "bidirectional"))
      (node (ref "C2") (pin "1") (pinfunction "1_1") (pintype "passive"))
      (node (ref "D2") (pin "+") (pinfunction "+_+") (pintype "passive"))
      (node (ref "J1P") (pin "1") (pinfunction "1_1") (pintype "passive"))
      (node (ref "U2") (pin "3") (pinfunction "VBAT_3") (pintype "power_in"))
    )
    (net (code "60") (name "VBUS") (class "Default")
      (node (ref "C6") (pin "1") (pinfunction "1_1") (pintype "passive"))
      (node (ref "D1") (pin "+") (pinfunction "+_+") (pintype "passive"))
      (node (ref "LED2") (pin "+") (pinfunction "+_+") (pintype "passive"))
      (node (ref "U2") (pin "4") (pinfunction "VIN_4") (pintype "power_in"))
      (node (ref "U3") (pin "25") (pinfunction "VBUS_25") (pintype "bidirectional"))
      (node (ref "USB") (pin "VBUS") (pinfunction "VBUS_VBUS") (pintype "bidirectional"))
    )
    (net (code "61") (name "VCC") (class "Default")
      (node (ref "C102") (pin "2") (pinfunction "2_2") (pintype "passive"))
      (node (ref "C103") (pin "1") (pinfunction "1_1") (pintype "passive"))
      (node (ref "C17") (pin "+") (pinfunction "+_+") (pintype "passive"))
      (node (ref "C7") (pin "2") (pinfunction "2_2") (pintype "passive"))
      (node (ref "JP2") (pin "6") (pinfunction "6_6") (pintype "passive"))
      (node (ref "L1") (pin "1") (pinfunction "1_1") (pintype "passive"))
      (node (ref "L2") (pin "1") (pinfunction "1_1") (pintype "passive"))
      (node (ref "L3") (pin "1") (pinfunction "1_1") (pintype "passive"))
      (node (ref "U100") (pin "8") (pinfunction "VCC_8") (pintype "power_in"))
      (node (ref "VCC") (pin "2") (pinfunction "2_2") (pintype "passive"))
      (node (ref "Y101") (pin "1") (pinfunction "EN_1") (pintype "bidirectional"))
      (node (ref "Y101") (pin "4") (pinfunction "VCC_4") (pintype "bidirectional"))
    )
    (net (code "62") (name "VCCD") (class "Default")
      (node (ref "C13") (pin "1") (pinfunction "1_1") (pintype "passive"))
      (node (ref "U3") (pin "37") (pinfunction "VCCD_37") (pintype "bidirectional"))
    )
    (net (code "63") (name "VDDA") (class "Default")
      (node (ref "C8") (pin "1") (pinfunction "1_1") (pintype "passive"))
      (node (ref "C9") (pin "1") (pinfunction "1_1") (pintype "passive"))
      (node (ref "L1") (pin "2") (pinfunction "2_2") (pintype "passive"))
      (node (ref "U3") (pin "40") (pinfunction "VDDA_40") (pintype "bidirectional"))
    )
    (net (code "64") (name "VDDD") (class "Default")
      (node (ref "C10") (pin "1") (pinfunction "1_1") (pintype "passive"))
      (node (ref "C11") (pin "1") (pinfunction "1_1") (pintype "passive"))
      (node (ref "L2") (pin "2") (pinfunction "2_2") (pintype "passive"))
      (node (ref "U3") (pin "39") (pinfunction "VDDD_39") (pintype "bidirectional"))
    )
    (net (code "65") (name "VDDIO") (class "Default")
      (node (ref "C14") (pin "1") (pinfunction "1_1") (pintype "passive"))
      (node (ref "C15") (pin "1") (pinfunction "1_1") (pintype "passive"))
      (node (ref "L3") (pin "2") (pinfunction "2_2") (pintype "passive"))
      (node (ref "R10") (pin "2") (pinfunction "2_2") (pintype "passive"))
      (node (ref "R11") (pin "2") (pinfunction "2_2") (pintype "passive"))
      (node (ref "R9") (pin "2") (pinfunction "2_2") (pintype "passive"))
      (node (ref "U3") (pin "21") (pinfunction "VDDIO_21") (pintype "bidirectional"))
    )
    (net (code "66") (name "VIN") (class "Default")
      (node (ref "D1") (pin "-") (pinfunction "-_-") (pintype "passive"))
      (node (ref "D2") (pin "-") (pinfunction "-_-") (pintype "passive"))
      (node (ref "F1") (pin "1") (pinfunction "1_1") (pintype "bidirectional"))
    )
    (net (code "67") (name "unconnected-(BATTERY-PAD1-PadNC1)") (class "Default")
      (node (ref "BATTERY") (pin "NC1") (pinfunction "PAD1_NC1") (pintype "bidirectional"))
    )
    (net (code "68") (name "unconnected-(BATTERY-PAD2-PadNC2)") (class "Default")
      (node (ref "BATTERY") (pin "NC2") (pinfunction "PAD2_NC2") (pintype "bidirectional"))
    )
    (net (code "69") (name "unconnected-(J1-Pad1)") (class "Default")
      (node (ref "J1") (pin "1") (pinfunction "1_1") (pintype "passive"))
    )
    (net (code "70") (name "unconnected-(J1-Pad2)") (class "Default")
      (node (ref "J1") (pin "2") (pinfunction "2_2") (pintype "passive"))
    )
    (net (code "71") (name "unconnected-(J1-Pad3)") (class "Default")
      (node (ref "J1") (pin "3") (pinfunction "3_3") (pintype "passive"))
    )
    (net (code "72") (name "unconnected-(J1-Pad4)") (class "Default")
      (node (ref "J1") (pin "4") (pinfunction "4_4") (pintype "passive"))
    )
    (net (code "73") (name "unconnected-(J1-Pad5)") (class "Default")
      (node (ref "J1") (pin "5") (pinfunction "5_5") (pintype "passive"))
    )
    (net (code "74") (name "unconnected-(J1-Pad6)") (class "Default")
      (node (ref "J1") (pin "6") (pinfunction "6_6") (pintype "passive"))
    )
    (net (code "75") (name "unconnected-(J1-Pad7)") (class "Default")
      (node (ref "J1") (pin "7") (pinfunction "7_7") (pintype "passive"))
    )
    (net (code "76") (name "unconnected-(J1-Pad8)") (class "Default")
      (node (ref "J1") (pin "8") (pinfunction "8_8") (pintype "passive"))
    )
    (net (code "77") (name "unconnected-(J1-Pad9)") (class "Default")
      (node (ref "J1") (pin "9") (pinfunction "9_9") (pintype "passive"))
    )
    (net (code "78") (name "unconnected-(J1-Pad10)") (class "Default")
      (node (ref "J1") (pin "10") (pinfunction "10_10") (pintype "passive"))
    )
    (net (code "79") (name "unconnected-(J1-Pad11)") (class "Default")
      (node (ref "J1") (pin "11") (pinfunction "11_11") (pintype "passive"))
    )
    (net (code "80") (name "unconnected-(J1-Pad12)") (class "Default")
      (node (ref "J1") (pin "12") (pinfunction "12_12") (pintype "passive"))
    )
    (net (code "81") (name "unconnected-(J1-Pad13)") (class "Default")
      (node (ref "J1") (pin "13") (pinfunction "13_13") (pintype "passive"))
    )
    (net (code "82") (name "unconnected-(J1-Pad14)") (class "Default")
      (node (ref "J1") (pin "14") (pinfunction "14_14") (pintype "passive"))
    )
    (net (code "83") (name "unconnected-(J1-Pad15)") (class "Default")
      (node (ref "J1") (pin "15") (pinfunction "15_15") (pintype "passive"))
    )
    (net (code "84") (name "unconnected-(J1-Pad16)") (class "Default")
      (node (ref "J1") (pin "16") (pinfunction "16_16") (pintype "passive"))
    )
    (net (code "85") (name "unconnected-(JP2-Pad4)") (class "Default")
      (node (ref "JP2") (pin "4") (pinfunction "4_4") (pintype "passive"))
    )
    (net (code "86") (name "unconnected-(MIDI_IN-Pad1)") (class "Default")
      (node (ref "MIDI_IN") (pin "1") (pinfunction "1_1") (pintype "bidirectional"))
    )
    (net (code "87") (name "unconnected-(MIDI_IN-Pad2)") (class "Default")
      (node (ref "MIDI_IN") (pin "2") (pinfunction "2_2") (pintype "bidirectional"))
    )
    (net (code "88") (name "unconnected-(MIDI_IN-Pad3)") (class "Default")
      (node (ref "MIDI_IN") (pin "3") (pinfunction "3_3") (pintype "bidirectional"))
    )
    (net (code "89") (name "unconnected-(MIDI_OUT-Pad1)") (class "Default")
      (node (ref "MIDI_OUT") (pin "1") (pinfunction "1_1") (pintype "bidirectional"))
    )
    (net (code "90") (name "unconnected-(MIDI_OUT-Pad3)") (class "Default")
      (node (ref "MIDI_OUT") (pin "3") (pinfunction "3_3") (pintype "bidirectional"))
    )
    (net (code "91") (name "unconnected-(OK1-VE-Pad7)") (class "Default")
      (node (ref "OK1") (pin "7") (pinfunction "VE_7") (pintype "passive"))
    )
    (net (code "92") (name "unconnected-(U3-NC-Pad11)") (class "Default")
      (node (ref "U3") (pin "11") (pinfunction "NC_11") (pintype "bidirectional"))
    )
    (net (code "93") (name "unconnected-(U3-NC-Pad15)") (class "Default")
      (node (ref "U3") (pin "15") (pinfunction "NC_15") (pintype "bidirectional"))
    )
  )
)
